# ChipSheet1.net
KiCad netlist of a schematic drawn in Altium Designer
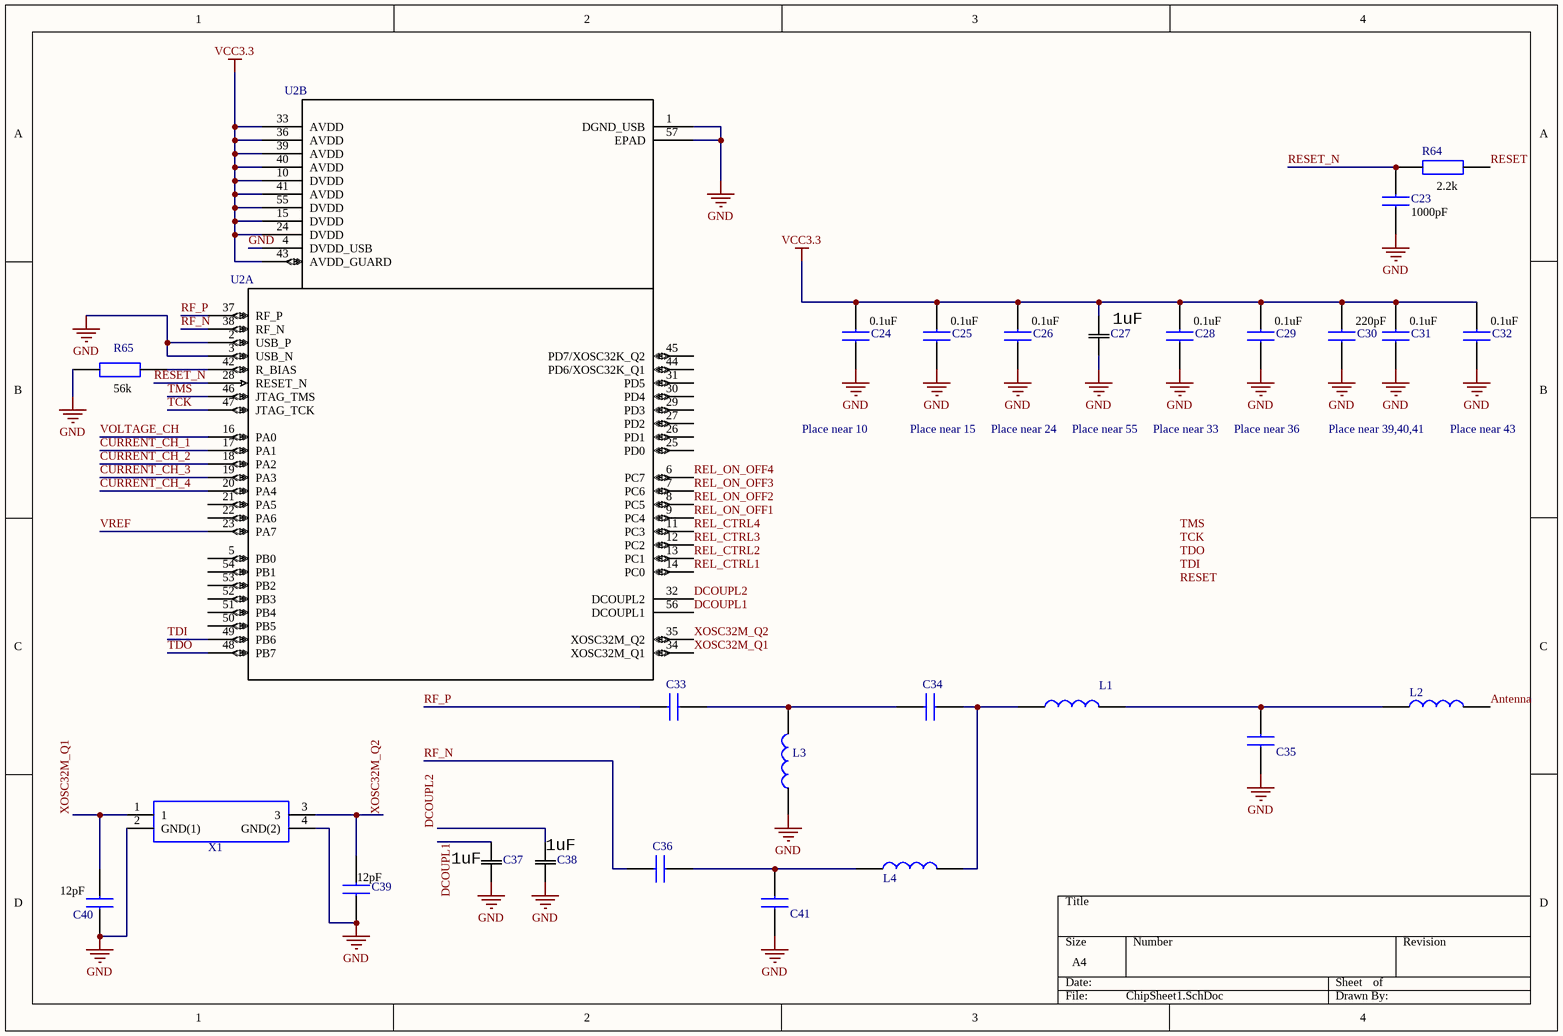
[diagram p0: ChipSheet1.SchDoc]

(export (version "E")
  (design (tool "Eeschema 10.0.6"))
  (components
    (comp (ref "C23")
      (value "1000pF")
      (footprint "CAPC1005X55N:CAPC1005X55N")
      (description "MURATA - GRM155R71H102KA01D - CAP, MLCC, X7R, 1NF, 50V, 0402")
      (fields
        (field (name "RS PART NUMBER") "7235266")
        (field (name "MANUFACTURER_PART_NUMBER") "GRM155R71H102KA01D")
      )
      (libsource (lib "GRM155R71H102KA01D") (part "GRM155R71H102KA01D"))
    )
    (comp (ref "C24")
      (value "0.1uF")
      (footprint "CAPC1005X55N:CAPC1005X55N")
      (fields
        (field (name "RS PART NUMBER") "8145265")
        (field (name "MANUFACTURER_PART_NUMBER") "GRM155R70J104KA01D")
      )
      (libsource (lib "GRM155R70J104KA01D") (part "GRM155R70J104KA01D"))
    )
    (comp (ref "C25")
      (value "0.1uF")
      (footprint "CAPC1005X55N:CAPC1005X55N")
      (fields
        (field (name "RS PART NUMBER") "8145265")
        (field (name "MANUFACTURER_PART_NUMBER") "GRM155R70J104KA01D")
      )
      (libsource (lib "GRM155R70J104KA01D") (part "GRM155R70J104KA01D"))
    )
    (comp (ref "C26")
      (value "0.1uF")
      (footprint "CAPC1005X55N:CAPC1005X55N")
      (fields
        (field (name "RS PART NUMBER") "8145265")
        (field (name "MANUFACTURER_PART_NUMBER") "GRM155R70J104KA01D")
      )
      (libsource (lib "GRM155R70J104KA01D") (part "GRM155R70J104KA01D"))
    )
    (comp (ref "C27")
      (value "1uF")
      (footprint "CAPC1005X55N:CAPC1005X55N")
      (description "Imported")
      (fields
        (field (name "MANUFACTURER_PART_NUMBER") "GRM155R61A105KE15D")
        (field (name "Comment") "GRM155R61A105KE1")
        (field (name "COPYRIGHT") "Copyright (C) 2016 Accelerated Designs. All rights reserved")
      )
      (libsource (lib "AltiumDesigner") (part "GRM155R61A105KE1"))
    )
    (comp (ref "C28")
      (value "0.1uF")
      (footprint "CAPC1005X55N:CAPC1005X55N")
      (fields
        (field (name "RS PART NUMBER") "8145265")
        (field (name "MANUFACTURER_PART_NUMBER") "GRM155R70J104KA01D")
      )
      (libsource (lib "GRM155R70J104KA01D") (part "GRM155R70J104KA01D"))
    )
    (comp (ref "C29")
      (value "0.1uF")
      (footprint "CAPC1005X55N:CAPC1005X55N")
      (fields
        (field (name "RS PART NUMBER") "8145265")
        (field (name "MANUFACTURER_PART_NUMBER") "GRM155R70J104KA01D")
      )
      (libsource (lib "GRM155R70J104KA01D") (part "GRM155R70J104KA01D"))
    )
    (comp (ref "C30")
      (value "220pF")
      (footprint "CAPC1005X55N:CAPC1005X55N")
      (fields
        (field (name "RS PART NUMBER") "6242941")
        (field (name "MANUFACTURER_PART_NUMBER") "GRM1555C1H221JA01D")
      )
      (libsource (lib "GRM1555C1H221JA01D") (part "GRM1555C1H221JA01D"))
    )
    (comp (ref "C31")
      (value "0.1uF")
      (footprint "CAPC1005X55N:CAPC1005X55N")
      (fields
        (field (name "RS PART NUMBER") "8145265")
        (field (name "MANUFACTURER_PART_NUMBER") "GRM155R70J104KA01D")
      )
      (libsource (lib "GRM155R70J104KA01D") (part "GRM155R70J104KA01D"))
    )
    (comp (ref "C32")
      (value "0.1uF")
      (footprint "CAPC1005X55N:CAPC1005X55N")
      (fields
        (field (name "RS PART NUMBER") "8145265")
        (field (name "MANUFACTURER_PART_NUMBER") "GRM155R70J104KA01D")
      )
      (libsource (lib "GRM155R70J104KA01D") (part "GRM155R70J104KA01D"))
    )
    (comp (ref "C33")
      (value "GRM1555C1H180JA01D")
      (footprint "CAPC1005X55N:CAPC1005X55N")
      (fields (field (name "RS PART NUMBER") "7235382"))
      (libsource (lib "GRM1555C1H180JA01D") (part "GRM1555C1H180JA01D"))
    )
    (comp (ref "C34")
      (value "GRM1555C1H1R0BA01D")
      (footprint "CAPC1005X55N:CAPC1005X55N")
      (fields (field (name "RS PART NUMBER") "7235335"))
      (libsource (lib "GRM1555C1H1R0BA01D") (part "GRM1555C1H1R0BA01D"))
    )
    (comp (ref "C35")
      (value "GRM1555C1H1R2CA01D")
      (footprint "CAPC1005X55N:CAPC1005X55N")
      (description "MURATA - GRM1555C1H1R2CA01D - CAP, MLCC, C0G/NP0, 1.2PF, 50V, 0402")
      (fields (field (name "RS PART NUMBER") "7235348"))
      (libsource (lib "GRM1555C1H1R2CA01D") (part "GRM1555C1H1R2CA01D"))
    )
    (comp (ref "C36")
      (value "GRM1555C1H180JA01D")
      (footprint "CAPC1005X55N:CAPC1005X55N")
      (fields (field (name "RS PART NUMBER") "7235382"))
      (libsource (lib "GRM1555C1H180JA01D") (part "GRM1555C1H180JA01D"))
    )
    (comp (ref "C37")
      (value "1uF")
      (footprint "CAPC1005X55N:CAPC1005X55N")
      (description "Imported")
      (fields
        (field (name "MANUFACTURER_PART_NUMBER") "GRM155R61A105KE15D")
        (field (name "Comment") "GRM155R61A105KE1")
        (field (name "COPYRIGHT") "Copyright (C) 2016 Accelerated Designs. All rights reserved")
      )
      (libsource (lib "AltiumDesigner") (part "GRM155R61A105KE1"))
    )
    (comp (ref "C38")
      (value "1uF")
      (footprint "CAPC1005X55N:CAPC1005X55N")
      (description "Imported")
      (fields
        (field (name "MANUFACTURER_PART_NUMBER") "GRM155R61A105KE15D")
        (field (name "Comment") "GRM155R61A105KE1")
        (field (name "COPYRIGHT") "Copyright (C) 2016 Accelerated Designs. All rights reserved")
      )
      (libsource (lib "AltiumDesigner") (part "GRM155R61A105KE1"))
    )
    (comp (ref "C39")
      (value "12pF")
      (footprint "CAPC1005X55N:CAPC1005X55N")
      (fields
        (field (name "RS PART NUMBER") "7235367")
        (field (name "MANUFACTURER_PART_NUMBER") "GRM1555C1H120JA01D")
      )
      (libsource (lib "GRM1555C1H120JA01D") (part "GRM1555C1H120JA01D"))
    )
    (comp (ref "C40")
      (value "12pF")
      (footprint "CAPC1005X55N:CAPC1005X55N")
      (fields
        (field (name "RS PART NUMBER") "7235367")
        (field (name "MANUFACTURER_PART_NUMBER") "GRM1555C1H120JA01D")
      )
      (libsource (lib "GRM1555C1H120JA01D") (part "GRM1555C1H120JA01D"))
    )
    (comp (ref "C41")
      (value "GRM1555C1H1R0BA01D")
      (footprint "CAPC1005X55N:CAPC1005X55N")
      (fields (field (name "RS PART NUMBER") "7235335"))
      (libsource (lib "GRM1555C1H1R0BA01D") (part "GRM1555C1H1R0BA01D"))
    )
    (comp (ref "L1")
      (value "LQG15HS2N0S02D")
      (footprint "INDC1005X55N:INDC1005X55N")
      (fields (field (name "RS PART NUMBER") "7926338"))
      (libsource (lib "LQG15HS2N0S02D") (part "LQG15HS2N0S02D"))
    )
    (comp (ref "L2")
      (value "LQG15HS3N3S02D")
      (footprint "INDC1005X55N:INDC1005X55N")
      (description "Murata Wire-wound SMD Inductor 0.0033 H 0.3nH 300mA Idc Q:8")
      (fields (field (name "RS PART NUMBER") "0107356"))
      (libsource (lib "LQG15HS3N3S02D") (part "LQG15HS3N3S02D"))
    )
    (comp (ref "L3")
      (value "LQG15HS2N0S02D")
      (footprint "INDC1005X55N:INDC1005X55N")
      (fields (field (name "RS PART NUMBER") "7926338"))
      (libsource (lib "LQG15HS2N0S02D") (part "LQG15HS2N0S02D"))
    )
    (comp (ref "L4")
      (value "LQG15HS2N0S02D")
      (footprint "INDC1005X55N:INDC1005X55N")
      (fields (field (name "RS PART NUMBER") "7926338"))
      (libsource (lib "LQG15HS2N0S02D") (part "LQG15HS2N0S02D"))
    )
    (comp (ref "R64")
      (value "2.2k")
      (footprint "RESC1005X40N:RESC1005X40N")
      (description "Vishay CRCW Series Thick Film Resistor 0402 Case 2.2k 5% 0.063W 200ppm/K")
      (fields
        (field (name "RS PART NUMBER") "8318680")
        (field (name "MANUFACTURER_PART_NUMBER") "CRCW04022K20JNED")
      )
      (libsource (lib "CRCW04022K20JNED") (part "CRCW04022K20JNED"))
    )
    (comp (ref "R65")
      (value "56k")
      (footprint "RESC1005X40N:RESC1005X40N")
      (description "Thick Film Resistors - SMD 56K OHM 1%")
      (fields (field (name "MANUFACTURER_PART_NUMBER") "RK73H1ETTP5602F"))
      (libsource (lib "RK73H1ETTP5602F") (part "RK73H1ETTP5602F"))
    )
    (comp (ref "U2")
      (value "CC2538_RTQ_56")
      (footprint "RTQ56_6P7X6P7")
      (description "Imported")
      (fields (field (name "MANUFACTURER_PART_NUMBER") "cc2538_rtq_56"))
      (libsource (lib "2017-09-27_22-50-45") (part "CC2538_RTQ_56"))
    )
    (comp (ref "X1")
      (value "FA-128_32.0000MF20X-K3")
      (footprint "FA128:FA128")
      (description "MHz range crystal unit, FA-128")
      (fields (field (name "MANUFACTURER_PART_NUMBER") "FA-128 32.0000MF20X-K3"))
      (libsource (lib "FA-128_32.0000MF20X-K3") (part "FA-128_32.0000MF20X-K3"))
    )
  )
  (nets
    (net (code "1") (name "/Antenna") (class "Default")
      (node (ref "L2") (pin "2") (pinfunction "2_2") (pintype "passive"))
    )
    (net (code "2") (name "/CURRENT_CH_1") (class "Default")
      (node (ref "U2") (pin "17") (pinfunction "PA1_17") (pintype "bidirectional"))
    )
    (net (code "3") (name "/CURRENT_CH_2") (class "Default")
      (node (ref "U2") (pin "18") (pinfunction "PA2_18") (pintype "bidirectional"))
    )
    (net (code "4") (name "/CURRENT_CH_3") (class "Default")
      (node (ref "U2") (pin "19") (pinfunction "PA3_19") (pintype "bidirectional"))
    )
    (net (code "5") (name "/CURRENT_CH_4") (class "Default")
      (node (ref "U2") (pin "20") (pinfunction "PA4_20") (pintype "bidirectional"))
    )
    (net (code "6") (name "/DCOUPL1") (class "Default")
      (node (ref "C37") (pin "2") (pinfunction "2_2") (pintype "passive"))
      (node (ref "U2") (pin "56") (pinfunction "DCOUPL1_56") (pintype "power_in"))
    )
    (net (code "7") (name "/DCOUPL2") (class "Default")
      (node (ref "C38") (pin "2") (pinfunction "2_2") (pintype "passive"))
      (node (ref "U2") (pin "32") (pinfunction "DCOUPL2_32") (pintype "power_in"))
    )
    (net (code "8") (name "/REL_CTRL1") (class "Default")
      (node (ref "U2") (pin "14") (pinfunction "PC0_14") (pintype "bidirectional"))
    )
    (net (code "9") (name "/REL_CTRL2") (class "Default")
      (node (ref "U2") (pin "13") (pinfunction "PC1_13") (pintype "bidirectional"))
    )
    (net (code "10") (name "/REL_CTRL3") (class "Default")
      (node (ref "U2") (pin "12") (pinfunction "PC2_12") (pintype "bidirectional"))
    )
    (net (code "11") (name "/REL_CTRL4") (class "Default")
      (node (ref "U2") (pin "11") (pinfunction "PC3_11") (pintype "bidirectional"))
    )
    (net (code "12") (name "/REL_ON_OFF1") (class "Default")
      (node (ref "U2") (pin "9") (pinfunction "PC4_9") (pintype "bidirectional"))
    )
    (net (code "13") (name "/REL_ON_OFF2") (class "Default")
      (node (ref "U2") (pin "8") (pinfunction "PC5_8") (pintype "bidirectional"))
    )
    (net (code "14") (name "/REL_ON_OFF3") (class "Default")
      (node (ref "U2") (pin "7") (pinfunction "PC6_7") (pintype "bidirectional"))
    )
    (net (code "15") (name "/REL_ON_OFF4") (class "Default")
      (node (ref "U2") (pin "6") (pinfunction "PC7_6") (pintype "bidirectional"))
    )
    (net (code "16") (name "/RESET") (class "Default")
      (node (ref "R64") (pin "2") (pinfunction "2_2") (pintype "passive"))
    )
    (net (code "17") (name "/RESET_N") (class "Default")
      (node (ref "C23") (pin "2") (pinfunction "2_2") (pintype "passive"))
      (node (ref "R64") (pin "1") (pinfunction "1_1") (pintype "passive"))
      (node (ref "U2") (pin "28") (pinfunction "RESET_N_28") (pintype "input"))
    )
    (net (code "18") (name "/RF_N") (class "Default")
      (node (ref "C36") (pin "1") (pinfunction "1_1") (pintype "passive"))
      (node (ref "U2") (pin "38") (pinfunction "RF_N_38") (pintype "bidirectional"))
    )
    (net (code "19") (name "/RF_P") (class "Default")
      (node (ref "C33") (pin "1") (pinfunction "1_1") (pintype "passive"))
      (node (ref "U2") (pin "37") (pinfunction "RF_P_37") (pintype "bidirectional"))
    )
    (net (code "20") (name "/TCK") (class "Default")
      (node (ref "U2") (pin "47") (pinfunction "JTAG_TCK_47") (pintype "bidirectional"))
    )
    (net (code "21") (name "/TDI") (class "Default")
      (node (ref "U2") (pin "49") (pinfunction "PB6_49") (pintype "bidirectional"))
    )
    (net (code "22") (name "/TDO") (class "Default")
      (node (ref "U2") (pin "48") (pinfunction "PB7_48") (pintype "bidirectional"))
    )
    (net (code "23") (name "/TMS") (class "Default")
      (node (ref "U2") (pin "46") (pinfunction "JTAG_TMS_46") (pintype "bidirectional"))
    )
    (net (code "24") (name "/VOLTAGE_CH") (class "Default")
      (node (ref "U2") (pin "16") (pinfunction "PA0_16") (pintype "bidirectional"))
    )
    (net (code "25") (name "/VREF") (class "Default")
      (node (ref "U2") (pin "23") (pinfunction "PA7_23") (pintype "bidirectional"))
    )
    (net (code "26") (name "/XOSC32M_Q1") (class "Default")
      (node (ref "C40") (pin "2") (pinfunction "2_2") (pintype "passive"))
      (node (ref "U2") (pin "34") (pinfunction "XOSC32M_Q1_34") (pintype "bidirectional"))
      (node (ref "X1") (pin "1") (pinfunction "1_1") (pintype "passive"))
    )
    (net (code "27") (name "/XOSC32M_Q2") (class "Default")
      (node (ref "C39") (pin "2") (pinfunction "2_2") (pintype "passive"))
      (node (ref "U2") (pin "35") (pinfunction "XOSC32M_Q2_35") (pintype "bidirectional"))
      (node (ref "X1") (pin "3") (pinfunction "3_3") (pintype "passive"))
    )
    (net (code "28") (name "GND") (class "Default")
      (node (ref "C23") (pin "1") (pinfunction "1_1") (pintype "passive"))
      (node (ref "C24") (pin "1") (pinfunction "1_1") (pintype "passive"))
      (node (ref "C25") (pin "1") (pinfunction "1_1") (pintype "passive"))
      (node (ref "C26") (pin "1") (pinfunction "1_1") (pintype "passive"))
      (node (ref "C27") (pin "1") (pinfunction "1_1") (pintype "passive"))
      (node (ref "C28") (pin "1") (pinfunction "1_1") (pintype "passive"))
      (node (ref "C29") (pin "1") (pinfunction "1_1") (pintype "passive"))
      (node (ref "C30") (pin "1") (pinfunction "1_1") (pintype "passive"))
      (node (ref "C31") (pin "1") (pinfunction "1_1") (pintype "passive"))
      (node (ref "C32") (pin "1") (pinfunction "1_1") (pintype "passive"))
      (node (ref "C35") (pin "1") (pinfunction "1_1") (pintype "passive"))
      (node (ref "C37") (pin "1") (pinfunction "1_1") (pintype "passive"))
      (node (ref "C38") (pin "1") (pinfunction "1_1") (pintype "passive"))
      (node (ref "C39") (pin "1") (pinfunction "1_1") (pintype "passive"))
      (node (ref "C40") (pin "1") (pinfunction "1_1") (pintype "passive"))
      (node (ref "C41") (pin "1") (pinfunction "1_1") (pintype "passive"))
      (node (ref "L3") (pin "1") (pinfunction "1_1") (pintype "passive"))
      (node (ref "R65") (pin "1") (pinfunction "1_1") (pintype "passive"))
      (node (ref "U2") (pin "1") (pinfunction "DGND_USB_1") (pintype "power_in"))
      (node (ref "U2") (pin "2") (pinfunction "USB_P_2") (pintype "bidirectional"))
      (node (ref "U2") (pin "3") (pinfunction "USB_N_3") (pintype "bidirectional"))
      (node (ref "U2") (pin "4") (pinfunction "DVDD_USB_4") (pintype "power_in"))
      (node (ref "U2") (pin "57") (pinfunction "EPAD_57") (pintype "passive"))
      (node (ref "X1") (pin "2") (pinfunction "GND(1)_2") (pintype "passive"))
      (node (ref "X1") (pin "4") (pinfunction "GND(2)_4") (pintype "passive"))
    )
    (net (code "29") (name "Net-(C33-Pad2)") (class "Default")
      (node (ref "C33") (pin "2") (pinfunction "2_2") (pintype "passive"))
      (node (ref "C34") (pin "1") (pinfunction "1_1") (pintype "passive"))
      (node (ref "L3") (pin "2") (pinfunction "2_2") (pintype "passive"))
    )
    (net (code "30") (name "Net-(C34-Pad2)") (class "Default")
      (node (ref "C34") (pin "2") (pinfunction "2_2") (pintype "passive"))
      (node (ref "L1") (pin "1") (pinfunction "1_1") (pintype "passive"))
      (node (ref "L4") (pin "2") (pinfunction "2_2") (pintype "passive"))
    )
    (net (code "31") (name "Net-(C35-Pad2)") (class "Default")
      (node (ref "C35") (pin "2") (pinfunction "2_2") (pintype "passive"))
      (node (ref "L1") (pin "2") (pinfunction "2_2") (pintype "passive"))
      (node (ref "L2") (pin "1") (pinfunction "1_1") (pintype "passive"))
    )
    (net (code "32") (name "Net-(C36-Pad2)") (class "Default")
      (node (ref "C36") (pin "2") (pinfunction "2_2") (pintype "passive"))
      (node (ref "C41") (pin "2") (pinfunction "2_2") (pintype "passive"))
      (node (ref "L4") (pin "1") (pinfunction "1_1") (pintype "passive"))
    )
    (net (code "33") (name "Net-(U2A-R_BIAS)") (class "Default")
      (node (ref "R65") (pin "2") (pinfunction "2_2") (pintype "passive"))
      (node (ref "U2") (pin "42") (pinfunction "R_BIAS_42") (pintype "bidirectional"))
    )
    (net (code "34") (name "VCC3.3") (class "Default")
      (node (ref "C24") (pin "2") (pinfunction "2_2") (pintype "passive"))
      (node (ref "C25") (pin "2") (pinfunction "2_2") (pintype "passive"))
      (node (ref "C26") (pin "2") (pinfunction "2_2") (pintype "passive"))
      (node (ref "C27") (pin "2") (pinfunction "2_2") (pintype "passive"))
      (node (ref "C28") (pin "2") (pinfunction "2_2") (pintype "passive"))
      (node (ref "C29") (pin "2") (pinfunction "2_2") (pintype "passive"))
      (node (ref "C30") (pin "2") (pinfunction "2_2") (pintype "passive"))
      (node (ref "C31") (pin "2") (pinfunction "2_2") (pintype "passive"))
      (node (ref "C32") (pin "2") (pinfunction "2_2") (pintype "passive"))
      (node (ref "U2") (pin "10") (pinfunction "DVDD_10") (pintype "power_in"))
      (node (ref "U2") (pin "15") (pinfunction "DVDD_15") (pintype "power_in"))
      (node (ref "U2") (pin "24") (pinfunction "DVDD_24") (pintype "power_in"))
      (node (ref "U2") (pin "33") (pinfunction "AVDD_33") (pintype "power_in"))
      (node (ref "U2") (pin "36") (pinfunction "AVDD_36") (pintype "power_in"))
      (node (ref "U2") (pin "39") (pinfunction "AVDD_39") (pintype "power_in"))
      (node (ref "U2") (pin "40") (pinfunction "AVDD_40") (pintype "power_in"))
      (node (ref "U2") (pin "41") (pinfunction "AVDD_41") (pintype "power_in"))
      (node (ref "U2") (pin "43") (pinfunction "AVDD_GUARD_43") (pintype "bidirectional"))
      (node (ref "U2") (pin "55") (pinfunction "DVDD_55") (pintype "power_in"))
    )
    (net (code "35") (name "unconnected-(U2A-PA5-Pad21)") (class "Default")
      (node (ref "U2") (pin "21") (pinfunction "PA5_21") (pintype "bidirectional"))
    )
    (net (code "36") (name "unconnected-(U2A-PA6-Pad22)") (class "Default")
      (node (ref "U2") (pin "22") (pinfunction "PA6_22") (pintype "bidirectional"))
    )
    (net (code "37") (name "unconnected-(U2A-PB0-Pad5)") (class "Default")
      (node (ref "U2") (pin "5") (pinfunction "PB0_5") (pintype "bidirectional"))
    )
    (net (code "38") (name "unconnected-(U2A-PB1-Pad54)") (class "Default")
      (node (ref "U2") (pin "54") (pinfunction "PB1_54") (pintype "bidirectional"))
    )
    (net (code "39") (name "unconnected-(U2A-PB2-Pad53)") (class "Default")
      (node (ref "U2") (pin "53") (pinfunction "PB2_53") (pintype "bidirectional"))
    )
    (net (code "40") (name "unconnected-(U2A-PB3-Pad52)") (class "Default")
      (node (ref "U2") (pin "52") (pinfunction "PB3_52") (pintype "bidirectional"))
    )
    (net (code "41") (name "unconnected-(U2A-PB4-Pad51)") (class "Default")
      (node (ref "U2") (pin "51") (pinfunction "PB4_51") (pintype "bidirectional"))
    )
    (net (code "42") (name "unconnected-(U2A-PB5-Pad50)") (class "Default")
      (node (ref "U2") (pin "50") (pinfunction "PB5_50") (pintype "bidirectional"))
    )
    (net (code "43") (name "unconnected-(U2A-PD0-Pad25)") (class "Default")
      (node (ref "U2") (pin "25") (pinfunction "PD0_25") (pintype "bidirectional"))
    )
    (net (code "44") (name "unconnected-(U2A-PD1-Pad26)") (class "Default")
      (node (ref "U2") (pin "26") (pinfunction "PD1_26") (pintype "bidirectional"))
    )
    (net (code "45") (name "unconnected-(U2A-PD2-Pad27)") (class "Default")
      (node (ref "U2") (pin "27") (pinfunction "PD2_27") (pintype "bidirectional"))
    )
    (net (code "46") (name "unconnected-(U2A-PD3-Pad29)") (class "Default")
      (node (ref "U2") (pin "29") (pinfunction "PD3_29") (pintype "bidirectional"))
    )
    (net (code "47") (name "unconnected-(U2A-PD4-Pad30)") (class "Default")
      (node (ref "U2") (pin "30") (pinfunction "PD4_30") (pintype "bidirectional"))
    )
    (net (code "48") (name "unconnected-(U2A-PD5-Pad31)") (class "Default")
      (node (ref "U2") (pin "31") (pinfunction "PD5_31") (pintype "bidirectional"))
    )
    (net (code "49") (name "unconnected-(U2A-PD6{slash}XOSC32K_Q1-Pad44)") (class "Default")
      (node (ref "U2") (pin "44") (pinfunction "PD6/XOSC32K_Q1_44") (pintype "bidirectional"))
    )
    (net (code "50") (name "unconnected-(U2A-PD7{slash}XOSC32K_Q2-Pad45)") (class "Default")
      (node (ref "U2") (pin "45") (pinfunction "PD7/XOSC32K_Q2_45") (pintype "bidirectional"))
    )
  )
)
